# Spark_Stick_v1_0.net
KiCad netlist of a schematic drawn in EAGLE
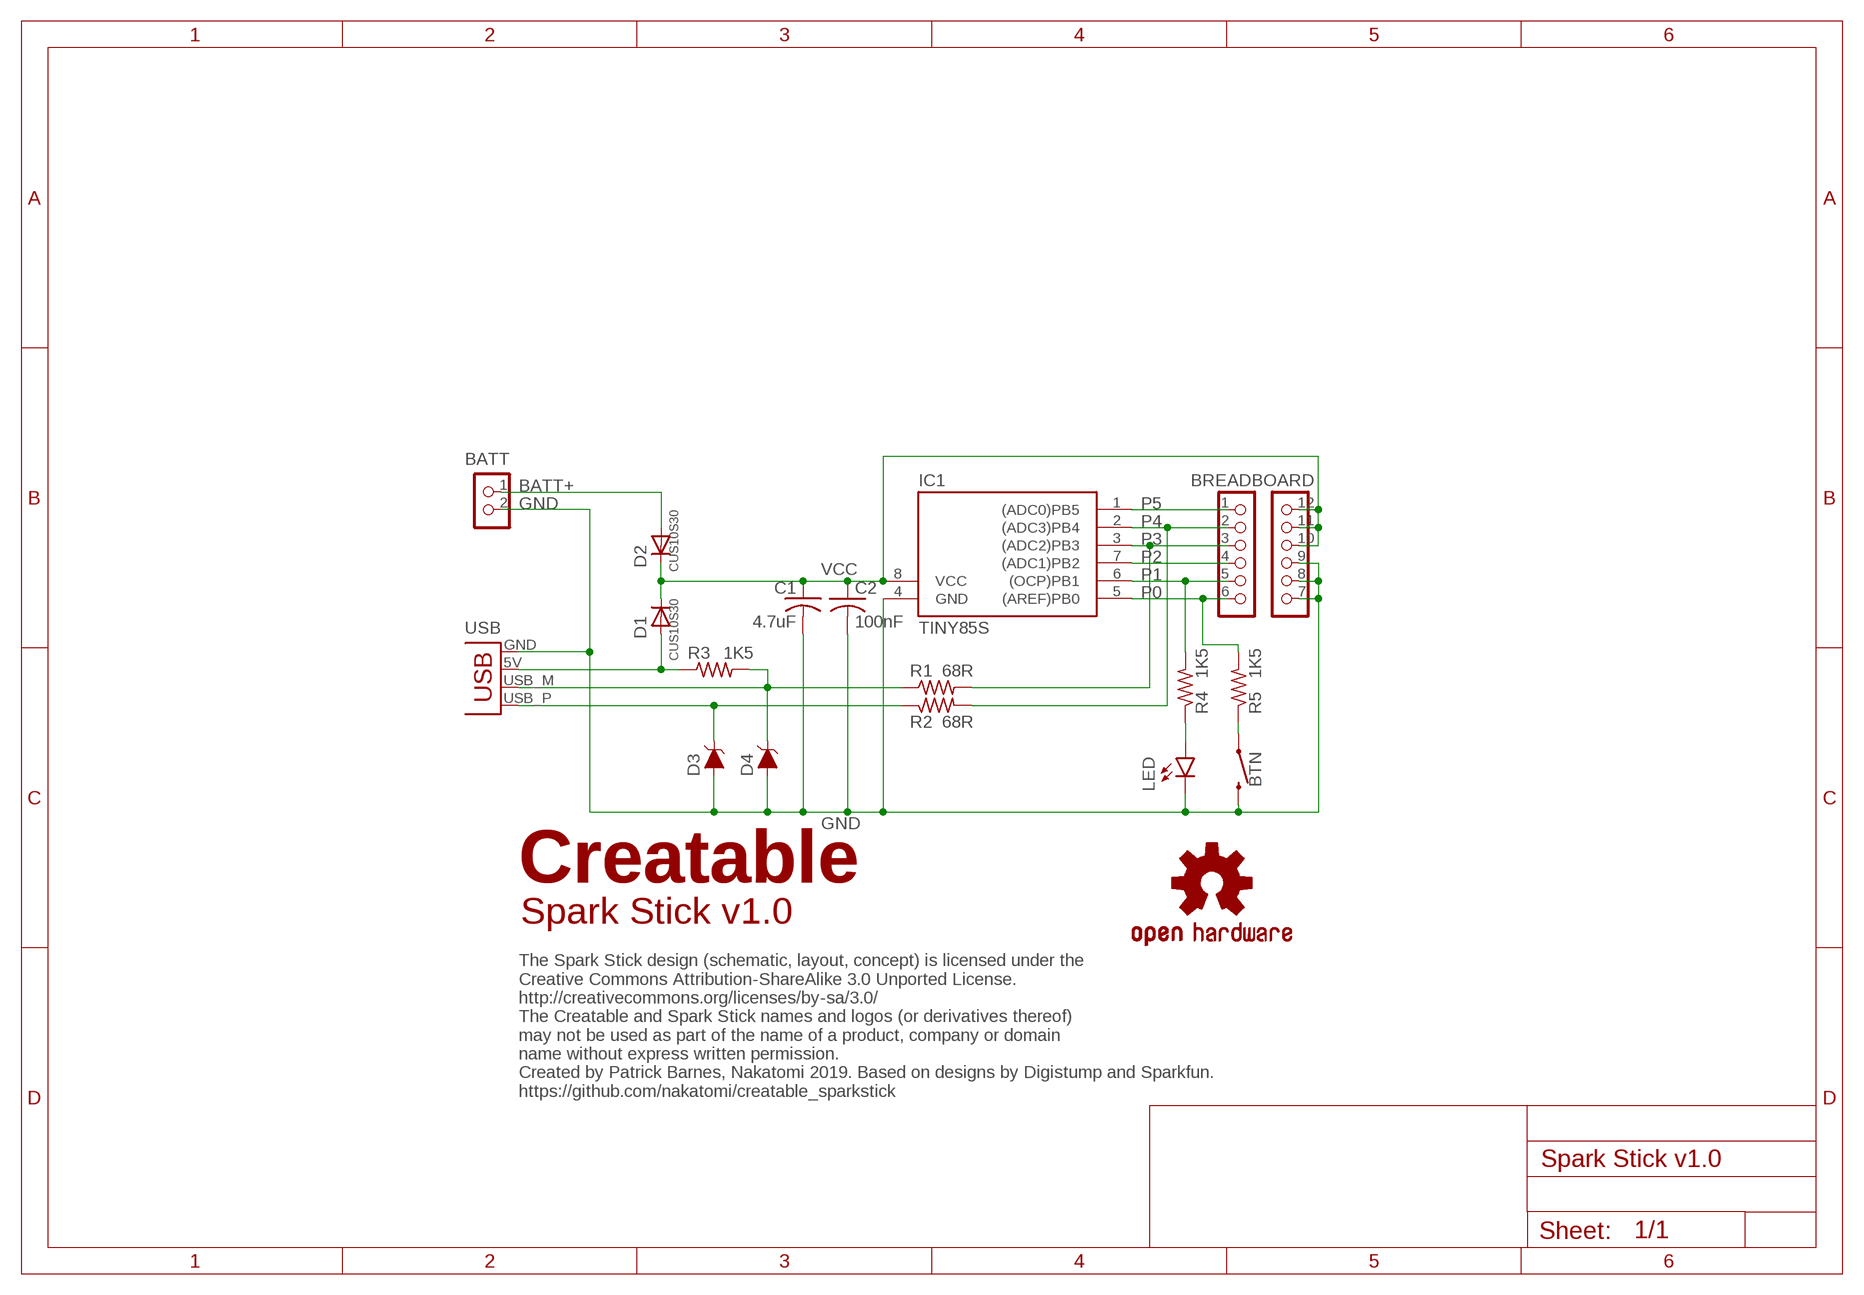
[diagram p0: schematic, sheet 1]

(export (version "E")
  (design (tool "Eeschema 10.0.6"))
  (components
    (comp (ref "BATT")
      (value "CON_HEADER_1X02ROUND")
      (footprint "eagle-import:CON_HEADER_M1X2_ROUND")
      (libsource (lib "eagle-import") (part "CON_HEADER_1X02ROUND"))
    )
    (comp (ref "BREADBOARD")
      (value "CON_HEADER_2X06")
      (footprint "eagle-import:CON_HEADER_M2X6_BREADBOARD")
      (libsource (lib "eagle-import") (part "CON_HEADER_2X06"))
    )
    (comp (ref "BTN")
      (value "MOMENTARY-SWITCH-SPST-PTS810")
      (footprint "eagle-import:PTS810SJG250SMTRLFS")
      (libsource (lib "eagle-import") (part "MOMENTARY-SWITCH-SPST-PTS810"))
    )
    (comp (ref "C1")
      (value "4.7uF")
      (footprint "eagle-import:C0805K")
      (libsource (lib "eagle-import") (part "CAPACITORC0805K"))
    )
    (comp (ref "C2")
      (value "100nF")
      (footprint "eagle-import:C0805K")
      (libsource (lib "eagle-import") (part "CAPACITORC0805K"))
    )
    (comp (ref "D1")
      (value "CUS10S30")
      (footprint "eagle-import:SOD-323F")
      (libsource (lib "eagle-import") (part "DIODESOD-323F"))
    )
    (comp (ref "D2")
      (value "CUS10S30")
      (footprint "eagle-import:SOD-323F")
      (libsource (lib "eagle-import") (part "DIODESOD-323F"))
    )
    (comp (ref "D3")
      (value "DIODE-ZENER-SOD-323F")
      (footprint "eagle-import:SOD-323F")
      (libsource (lib "eagle-import") (part "DIODE-ZENER-SOD-323F"))
    )
    (comp (ref "D4")
      (value "DIODE-ZENER-SOD-323F")
      (footprint "eagle-import:SOD-323F")
      (libsource (lib "eagle-import") (part "DIODE-ZENER-SOD-323F"))
    )
    (comp (ref "IC1")
      (value "TINY85S")
      (footprint "eagle-import:SOIC8")
      (fields (field (name "MPN") "ATTINY85-20SU"))
      (libsource (lib "eagle-import") (part "TINY85S"))
    )
    (comp (ref "LED")
      (value "RED LED")
      (footprint "eagle-import:LED-0603")
      (libsource (lib "eagle-import") (part "LED0603"))
    )
    (comp (ref "LOGO1")
      (value "OSHW-LOGOM")
      (footprint "eagle-import:OSHW-LOGO-M")
      (libsource (lib "eagle-import") (part "OSHW-LOGOM"))
    )
    (comp (ref "LOGO_2A")
      (value "LOGO_CREATABLECREAT")
      (footprint "eagle-import:LOGO_CREATABLE_CREAT")
      (libsource (lib "eagle-import") (part "LOGO_CREATABLECREAT"))
    )
    (comp (ref "LOGO_2B")
      (value "LOGO_CREATABLEABLE")
      (footprint "eagle-import:LOGO_CREATABLE_ABLE")
      (libsource (lib "eagle-import") (part "LOGO_CREATABLEABLE"))
    )
    (comp (ref "R1")
      (value "68R")
      (footprint "eagle-import:R0603")
      (libsource (lib "eagle-import") (part "RESISTORR0603"))
    )
    (comp (ref "R2")
      (value "68R")
      (footprint "eagle-import:R0603")
      (libsource (lib "eagle-import") (part "RESISTORR0603"))
    )
    (comp (ref "R3")
      (value "1K5")
      (footprint "eagle-import:R0603")
      (libsource (lib "eagle-import") (part "RESISTORR0603"))
    )
    (comp (ref "R4")
      (value "1K5")
      (footprint "eagle-import:R0603")
      (libsource (lib "eagle-import") (part "RESISTORR0603"))
    )
    (comp (ref "R5")
      (value "1K5")
      (footprint "eagle-import:R0603")
      (libsource (lib "eagle-import") (part "RESISTORR0603"))
    )
    (comp (ref "USB")
      (value "MICRO USB")
      (footprint "eagle-import:SPARKFUN-CONNECTORS_USB-A-PCB")
      (libsource (lib "eagle-import") (part "SPARKFUN-CONNECTORS_USBPCB"))
    )
  )
  (nets
    (net (code "1") (name "/BATT+") (class "Default")
      (node (ref "BATT") (pin "1") (pinfunction "1_1") (pintype "bidirectional"))
      (node (ref "D2") (pin "A") (pinfunction "A_A") (pintype "passive"))
    )
    (net (code "2") (name "/GND") (class "Default")
      (node (ref "BATT") (pin "2") (pinfunction "2_2") (pintype "bidirectional"))
      (node (ref "BREADBOARD") (pin "7") (pinfunction "7_7") (pintype "bidirectional"))
      (node (ref "BREADBOARD") (pin "8") (pinfunction "8_8") (pintype "bidirectional"))
      (node (ref "BREADBOARD") (pin "9") (pinfunction "9_9") (pintype "bidirectional"))
      (node (ref "BTN") (pin "3") (pinfunction "2_3") (pintype "passive"))
      (node (ref "BTN") (pin "4") (pinfunction "2_4") (pintype "passive"))
      (node (ref "C1") (pin "2") (pinfunction "2_2") (pintype "passive"))
      (node (ref "C2") (pin "2") (pinfunction "2_2") (pintype "passive"))
      (node (ref "D3") (pin "A") (pinfunction "A_A") (pintype "passive"))
      (node (ref "D4") (pin "A") (pinfunction "A_A") (pintype "passive"))
      (node (ref "IC1") (pin "4") (pinfunction "GND_4") (pintype "power_in"))
      (node (ref "LED") (pin "C") (pinfunction "C_C") (pintype "passive"))
      (node (ref "USB") (pin "GND") (pinfunction "GND_GND") (pintype "bidirectional"))
    )
    (net (code "3") (name "/P0") (class "Default")
      (node (ref "BREADBOARD") (pin "6") (pinfunction "6_6") (pintype "bidirectional"))
      (node (ref "IC1") (pin "5") (pinfunction "(AREF)PB0_5") (pintype "bidirectional"))
      (node (ref "R5") (pin "2") (pinfunction "2_2") (pintype "passive"))
    )
    (net (code "4") (name "/P1") (class "Default")
      (node (ref "BREADBOARD") (pin "5") (pinfunction "5_5") (pintype "bidirectional"))
      (node (ref "IC1") (pin "6") (pinfunction "(OCP)PB1_6") (pintype "bidirectional"))
      (node (ref "R4") (pin "2") (pinfunction "2_2") (pintype "passive"))
    )
    (net (code "5") (name "/P2") (class "Default")
      (node (ref "BREADBOARD") (pin "4") (pinfunction "4_4") (pintype "bidirectional"))
      (node (ref "IC1") (pin "7") (pinfunction "(ADC1)PB2_7") (pintype "bidirectional"))
    )
    (net (code "6") (name "/P3") (class "Default")
      (node (ref "BREADBOARD") (pin "3") (pinfunction "3_3") (pintype "bidirectional"))
      (node (ref "IC1") (pin "3") (pinfunction "(ADC2)PB3_3") (pintype "bidirectional"))
      (node (ref "R1") (pin "2") (pinfunction "2_2") (pintype "passive"))
    )
    (net (code "7") (name "/P4") (class "Default")
      (node (ref "BREADBOARD") (pin "2") (pinfunction "2_2") (pintype "bidirectional"))
      (node (ref "IC1") (pin "2") (pinfunction "(ADC3)PB4_2") (pintype "bidirectional"))
      (node (ref "R2") (pin "2") (pinfunction "2_2") (pintype "passive"))
    )
    (net (code "8") (name "/P5") (class "Default")
      (node (ref "BREADBOARD") (pin "1") (pinfunction "1_1") (pintype "bidirectional"))
      (node (ref "IC1") (pin "1") (pinfunction "(ADC0)PB5_1") (pintype "bidirectional"))
    )
    (net (code "9") (name "/VCC") (class "Default")
      (node (ref "BREADBOARD") (pin "10") (pinfunction "10_10") (pintype "bidirectional"))
      (node (ref "BREADBOARD") (pin "11") (pinfunction "11_11") (pintype "bidirectional"))
      (node (ref "BREADBOARD") (pin "12") (pinfunction "12_12") (pintype "bidirectional"))
      (node (ref "C1") (pin "1") (pinfunction "1_1") (pintype "passive"))
      (node (ref "C2") (pin "1") (pinfunction "1_1") (pintype "passive"))
      (node (ref "D1") (pin "C") (pinfunction "C_C") (pintype "passive"))
      (node (ref "D2") (pin "C") (pinfunction "C_C") (pintype "passive"))
      (node (ref "IC1") (pin "8") (pinfunction "VCC_8") (pintype "power_in"))
    )
    (net (code "10") (name "Net-(BTN-1-Pad2)") (class "Default")
      (node (ref "BTN") (pin "1") (pinfunction "1_1") (pintype "passive"))
      (node (ref "BTN") (pin "2") (pinfunction "1_2") (pintype "passive"))
      (node (ref "R5") (pin "1") (pinfunction "1_1") (pintype "passive"))
    )
    (net (code "11") (name "Net-(LED-PadA)") (class "Default")
      (node (ref "LED") (pin "A") (pinfunction "A_A") (pintype "passive"))
      (node (ref "R4") (pin "1") (pinfunction "1_1") (pintype "passive"))
    )
    (net (code "12") (name "Net-(USB-D+)") (class "Default")
      (node (ref "D3") (pin "C") (pinfunction "C_C") (pintype "passive"))
      (node (ref "R2") (pin "1") (pinfunction "1_1") (pintype "passive"))
      (node (ref "USB") (pin "USB_P") (pinfunction "D+_USB_P") (pintype "bidirectional"))
    )
    (net (code "13") (name "Net-(USB-D-)") (class "Default")
      (node (ref "D4") (pin "C") (pinfunction "C_C") (pintype "passive"))
      (node (ref "R1") (pin "1") (pinfunction "1_1") (pintype "passive"))
      (node (ref "R3") (pin "2") (pinfunction "2_2") (pintype "passive"))
      (node (ref "USB") (pin "USB_M") (pinfunction "D-_USB_M") (pintype "bidirectional"))
    )
    (net (code "14") (name "Net-(USB-VBUS)") (class "Default")
      (node (ref "D1") (pin "A") (pinfunction "A_A") (pintype "passive"))
      (node (ref "R3") (pin "1") (pinfunction "1_1") (pintype "passive"))
      (node (ref "USB") (pin "5V") (pinfunction "VBUS_5V") (pintype "bidirectional"))
    )
  )
)
